# ADC_part2.net
KiCad netlist of a schematic drawn in Altium Designer
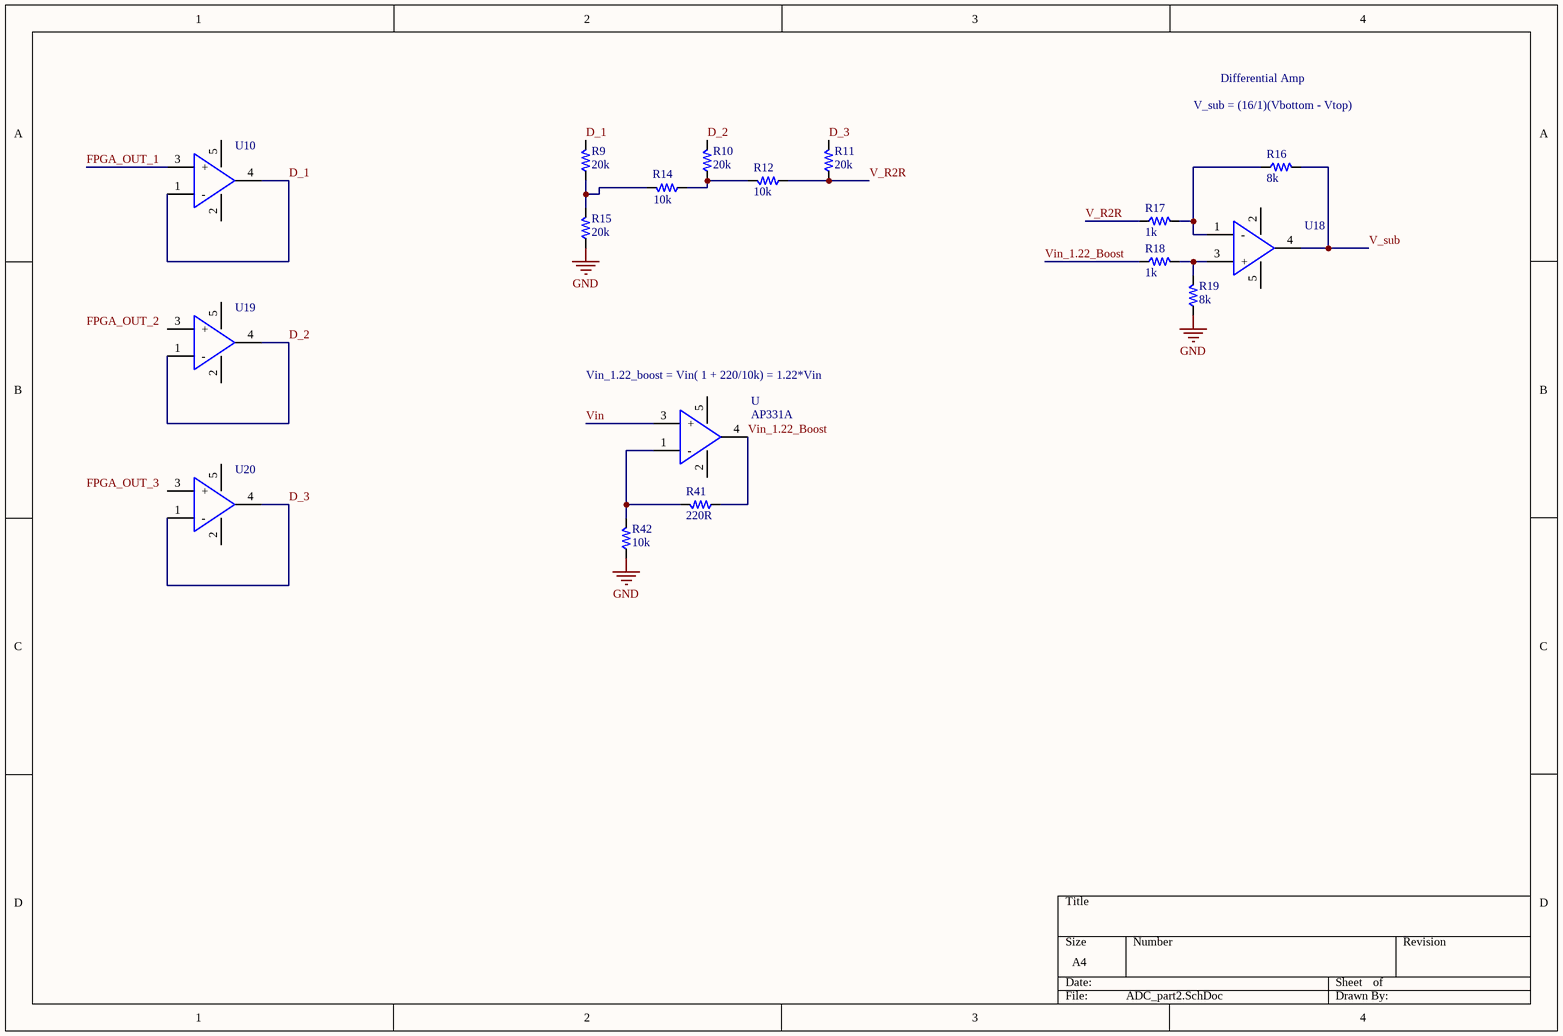
[diagram p0: ADC_part2.SchDoc]

(export (version "E")
  (design (tool "Eeschema 10.0.6"))
  (components
    (comp (ref "R9")
      (value "20k")
      (footprint "PCB_GENERIC_SMD_0603")
      (description "RES 0603 100ohm 5% 63mW")
      (fields (field (name "TOLERANCE") "5%") (field (name "POWER") "63mW"))
      (libsource (lib "RES") (part "R060-00101-05"))
    )
    (comp (ref "R10")
      (value "20k")
      (footprint "PCB_GENERIC_SMD_0603")
      (description "RES 0603 100ohm 5% 63mW")
      (fields (field (name "TOLERANCE") "5%") (field (name "POWER") "63mW"))
      (libsource (lib "RES") (part "R060-00101-05"))
    )
    (comp (ref "R11")
      (value "20k")
      (footprint "PCB_GENERIC_SMD_0603")
      (description "RES 0603 100ohm 5% 63mW")
      (fields (field (name "TOLERANCE") "5%") (field (name "POWER") "63mW"))
      (libsource (lib "RES") (part "R060-00101-05"))
    )
    (comp (ref "R12")
      (value "10k")
      (footprint "PCB_GENERIC_SMD_0603")
      (description "RES 0603 100ohm 5% 63mW")
      (fields (field (name "TOLERANCE") "5%") (field (name "POWER") "63mW"))
      (libsource (lib "RES") (part "R060-00101-05"))
    )
    (comp (ref "R14")
      (value "10k")
      (footprint "PCB_GENERIC_SMD_0603")
      (description "RES 0603 100ohm 5% 63mW")
      (fields (field (name "TOLERANCE") "5%") (field (name "POWER") "63mW"))
      (libsource (lib "RES") (part "R060-00101-05"))
    )
    (comp (ref "R15")
      (value "20k")
      (footprint "PCB_GENERIC_SMD_0603")
      (description "RES 0603 100ohm 5% 63mW")
      (fields (field (name "TOLERANCE") "5%") (field (name "POWER") "63mW"))
      (libsource (lib "RES") (part "R060-00101-05"))
    )
    (comp (ref "R16")
      (value "8k")
      (footprint "PCB_GENERIC_SMD_0603")
      (description "RES 0603 100ohm 5% 63mW")
      (fields (field (name "TOLERANCE") "5%") (field (name "POWER") "63mW"))
      (libsource (lib "RES") (part "R060-00101-05"))
    )
    (comp (ref "R17")
      (value "1k")
      (footprint "PCB_GENERIC_SMD_0603")
      (description "RES 0603 100ohm 5% 63mW")
      (fields (field (name "TOLERANCE") "5%") (field (name "POWER") "63mW"))
      (libsource (lib "RES") (part "R060-00101-05"))
    )
    (comp (ref "R18")
      (value "1k")
      (footprint "PCB_GENERIC_SMD_0603")
      (description "RES 0603 100ohm 5% 63mW")
      (fields (field (name "TOLERANCE") "5%") (field (name "POWER") "63mW"))
      (libsource (lib "RES") (part "R060-00101-05"))
    )
    (comp (ref "R19")
      (value "8k")
      (footprint "PCB_GENERIC_SMD_0603")
      (description "RES 0603 100ohm 5% 63mW")
      (fields (field (name "TOLERANCE") "5%") (field (name "POWER") "63mW"))
      (libsource (lib "RES") (part "R060-00101-05"))
    )
    (comp (ref "R41")
      (value "220R")
      (footprint "PCB_GENERIC_SMD_0603")
      (description "RES 0603 100ohm 5% 63mW")
      (fields (field (name "TOLERANCE") "5%") (field (name "POWER") "63mW"))
      (libsource (lib "RES") (part "R060-00101-05"))
    )
    (comp (ref "R42")
      (value "10k")
      (footprint "PCB_GENERIC_SMD_0603")
      (description "RES 0603 100ohm 5% 63mW")
      (fields (field (name "TOLERANCE") "5%") (field (name "POWER") "63mW"))
      (libsource (lib "RES") (part "R060-00101-05"))
    )
    (comp (ref "U")
      (value "AP331A")
      (footprint "SOT95P285X130-5N")
      (description "Single Channel Comparator, Open Drain, SC-74A/SOT-753")
      (libsource (lib "Op_Amp") (part "AP331A"))
    )
    (comp (ref "U10")
      (value "AP331A")
      (footprint "SOT95P285X130-5N")
      (description "Single Channel Comparator, Open Drain, SC-74A/SOT-753")
      (libsource (lib "Op_Amp") (part "AP331A"))
    )
    (comp (ref "U18")
      (value "AP331A")
      (footprint "SOT95P285X130-5N")
      (description "Single Channel Comparator, Open Drain, SC-74A/SOT-753")
      (libsource (lib "Op_Amp") (part "AP331A"))
    )
    (comp (ref "U19")
      (value "AP331A")
      (footprint "SOT95P285X130-5N")
      (description "Single Channel Comparator, Open Drain, SC-74A/SOT-753")
      (libsource (lib "Op_Amp") (part "AP331A"))
    )
    (comp (ref "U20")
      (value "AP331A")
      (footprint "SOT95P285X130-5N")
      (description "Single Channel Comparator, Open Drain, SC-74A/SOT-753")
      (libsource (lib "Op_Amp") (part "AP331A"))
    )
  )
  (nets
    (net (code "1") (name "/D_1") (class "Default")
      (node (ref "R9") (pin "2") (pinfunction "2_2") (pintype "passive"))
      (node (ref "U10") (pin "1") (pinfunction "-_1") (pintype "passive"))
      (node (ref "U10") (pin "4") (pinfunction "VOUT_4") (pintype "passive"))
    )
    (net (code "2") (name "/D_2") (class "Default")
      (node (ref "R10") (pin "2") (pinfunction "2_2") (pintype "passive"))
      (node (ref "U19") (pin "1") (pinfunction "-_1") (pintype "passive"))
      (node (ref "U19") (pin "4") (pinfunction "VOUT_4") (pintype "passive"))
    )
    (net (code "3") (name "/D_3") (class "Default")
      (node (ref "R11") (pin "2") (pinfunction "2_2") (pintype "passive"))
      (node (ref "U20") (pin "1") (pinfunction "-_1") (pintype "passive"))
      (node (ref "U20") (pin "4") (pinfunction "VOUT_4") (pintype "passive"))
    )
    (net (code "4") (name "/FPGA_OUT_1") (class "Default")
      (node (ref "U10") (pin "3") (pinfunction "+_3") (pintype "passive"))
    )
    (net (code "7") (name "/V_R2R") (class "Default")
      (node (ref "R11") (pin "1") (pinfunction "1_1") (pintype "passive"))
      (node (ref "R12") (pin "1") (pinfunction "1_1") (pintype "passive"))
      (node (ref "R17") (pin "1") (pinfunction "1_1") (pintype "passive"))
    )
    (net (code "8") (name "/V_sub") (class "Default")
      (node (ref "R16") (pin "2") (pinfunction "2_2") (pintype "passive"))
      (node (ref "U18") (pin "4") (pinfunction "VOUT_4") (pintype "passive"))
    )
    (net (code "9") (name "/Vin") (class "Default")
      (node (ref "U") (pin "3") (pinfunction "+_3") (pintype "passive"))
    )
    (net (code "10") (name "/Vin_1.22_Boost") (class "Default")
      (node (ref "R18") (pin "1") (pinfunction "1_1") (pintype "passive"))
      (node (ref "R41") (pin "1") (pinfunction "1_1") (pintype "passive"))
      (node (ref "U") (pin "4") (pinfunction "VOUT_4") (pintype "passive"))
    )
    (net (code "11") (name "GND") (class "Default")
      (node (ref "R15") (pin "1") (pinfunction "1_1") (pintype "passive"))
      (node (ref "R19") (pin "1") (pinfunction "1_1") (pintype "passive"))
      (node (ref "R42") (pin "1") (pinfunction "1_1") (pintype "passive"))
    )
    (net (code "12") (name "Net-(R10-Pad1)") (class "Default")
      (node (ref "R10") (pin "1") (pinfunction "1_1") (pintype "passive"))
      (node (ref "R12") (pin "2") (pinfunction "2_2") (pintype "passive"))
      (node (ref "R14") (pin "1") (pinfunction "1_1") (pintype "passive"))
    )
    (net (code "13") (name "Net-(R14-Pad2)") (class "Default")
      (node (ref "R14") (pin "2") (pinfunction "2_2") (pintype "passive"))
      (node (ref "R15") (pin "2") (pinfunction "2_2") (pintype "passive"))
      (node (ref "R9") (pin "1") (pinfunction "1_1") (pintype "passive"))
    )
    (net (code "14") (name "Net-(U--)") (class "Default")
      (node (ref "R41") (pin "2") (pinfunction "2_2") (pintype "passive"))
      (node (ref "R42") (pin "2") (pinfunction "2_2") (pintype "passive"))
      (node (ref "U") (pin "1") (pinfunction "-_1") (pintype "passive"))
    )
    (net (code "15") (name "Net-(U18-+)") (class "Default")
      (node (ref "R18") (pin "2") (pinfunction "2_2") (pintype "passive"))
      (node (ref "R19") (pin "2") (pinfunction "2_2") (pintype "passive"))
      (node (ref "U18") (pin "3") (pinfunction "+_3") (pintype "passive"))
    )
    (net (code "16") (name "Net-(U18--)") (class "Default")
      (node (ref "R16") (pin "1") (pinfunction "1_1") (pintype "passive"))
      (node (ref "R17") (pin "2") (pinfunction "2_2") (pintype "passive"))
      (node (ref "U18") (pin "1") (pinfunction "-_1") (pintype "passive"))
    )
    (net (code "17") (name "unconnected-(U-GND-Pad2)") (class "Default")
      (node (ref "U") (pin "2") (pinfunction "GND_2") (pintype "passive"))
    )
    (net (code "18") (name "unconnected-(U-VCC-Pad5)") (class "Default")
      (node (ref "U") (pin "5") (pinfunction "VCC_5") (pintype "passive"))
    )
    (net (code "19") (name "unconnected-(U10-GND-Pad2)") (class "Default")
      (node (ref "U10") (pin "2") (pinfunction "GND_2") (pintype "passive"))
    )
    (net (code "20") (name "unconnected-(U10-VCC-Pad5)") (class "Default")
      (node (ref "U10") (pin "5") (pinfunction "VCC_5") (pintype "passive"))
    )
    (net (code "21") (name "unconnected-(U18-GND-Pad2)") (class "Default")
      (node (ref "U18") (pin "2") (pinfunction "GND_2") (pintype "passive"))
    )
    (net (code "22") (name "unconnected-(U18-VCC-Pad5)") (class "Default")
      (node (ref "U18") (pin "5") (pinfunction "VCC_5") (pintype "passive"))
    )
    (net (code "23") (name "unconnected-(U19-+-Pad3)") (class "Default")
      (node (ref "U19") (pin "3") (pinfunction "+_3") (pintype "passive"))
    )
    (net (code "24") (name "unconnected-(U19-GND-Pad2)") (class "Default")
      (node (ref "U19") (pin "2") (pinfunction "GND_2") (pintype "passive"))
    )
    (net (code "25") (name "unconnected-(U19-VCC-Pad5)") (class "Default")
      (node (ref "U19") (pin "5") (pinfunction "VCC_5") (pintype "passive"))
    )
    (net (code "26") (name "unconnected-(U20-+-Pad3)") (class "Default")
      (node (ref "U20") (pin "3") (pinfunction "+_3") (pintype "passive"))
    )
    (net (code "27") (name "unconnected-(U20-GND-Pad2)") (class "Default")
      (node (ref "U20") (pin "2") (pinfunction "GND_2") (pintype "passive"))
    )
    (net (code "28") (name "unconnected-(U20-VCC-Pad5)") (class "Default")
      (node (ref "U20") (pin "5") (pinfunction "VCC_5") (pintype "passive"))
    )
  )
)
